# Water_Level_Indicator_shematic.net
KiCad netlist of a schematic drawn in Altium Designer
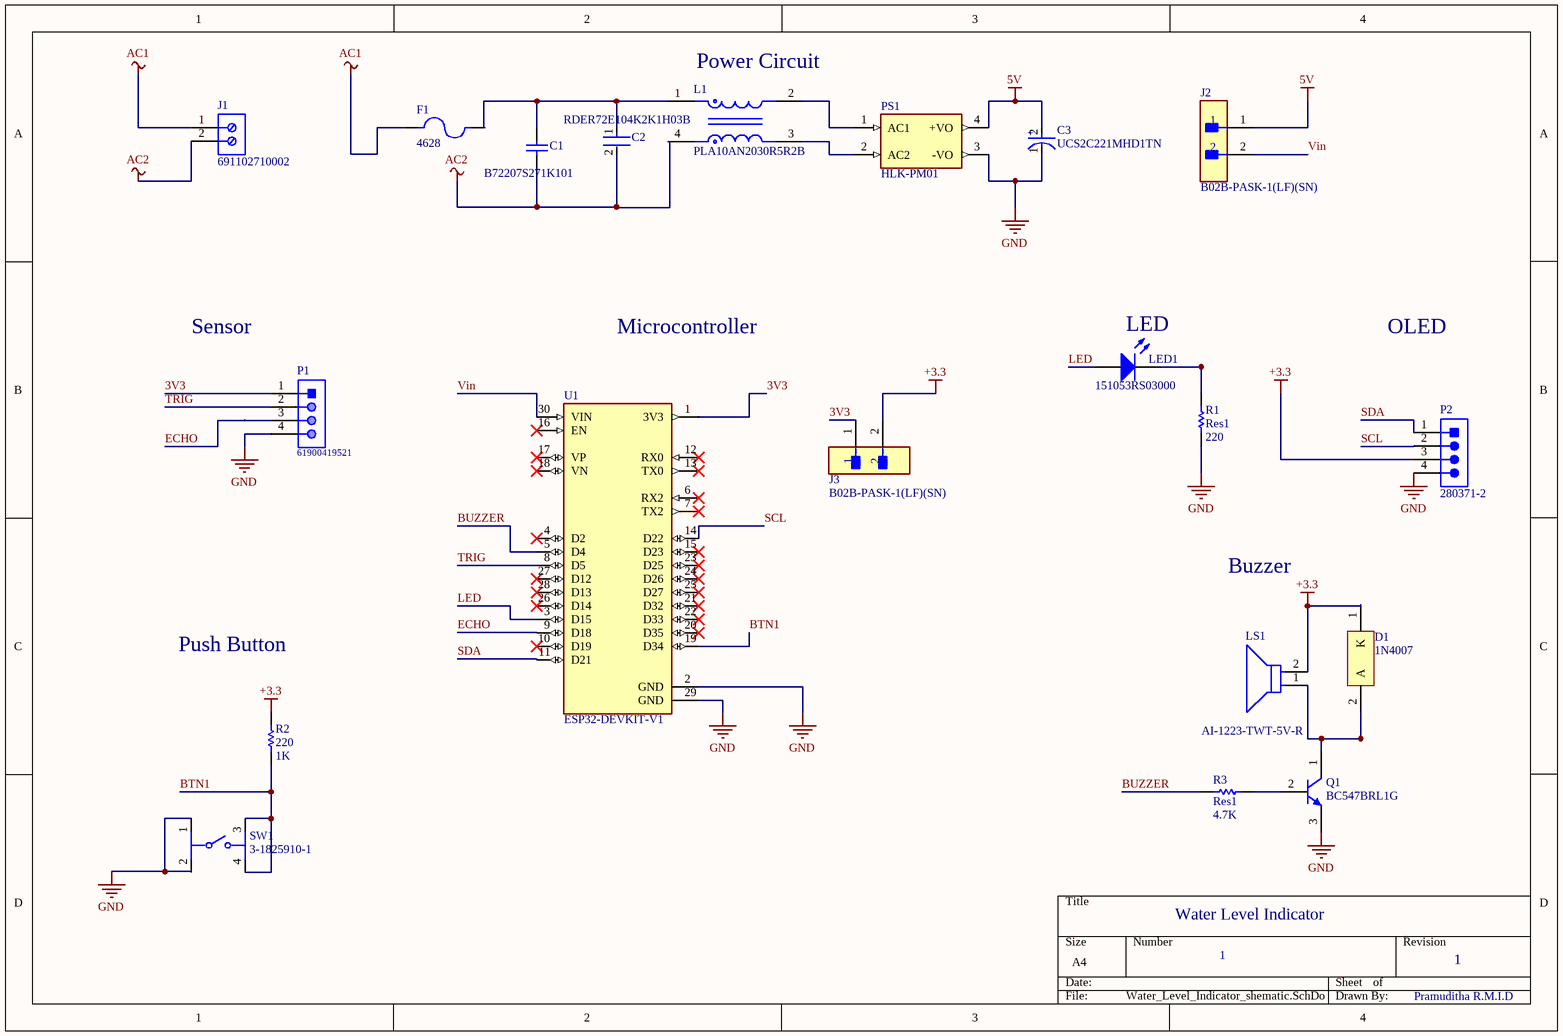
[diagram p0: Water_Level_Indicator_shematic.SchDoc]

(export (version "E")
  (design (tool "Eeschema 10.0.6"))
  (components
    (comp (ref "C1")
      (value "B72207S271K101")
      (footprint "TDK-S07K275")
      (description "Leaded Varistor, 110 pF, 275 Vrms, 1.2 KA, -40 to 85 degC, 2-Pin THD, RoHS, Bulk")
      (fields (field (name "MANUFACTURER") "TDK"))
      (libsource (lib "Altium Content Vault") (part "CAP-NP-2"))
    )
    (comp (ref "C2")
      (value "RDER72E104K2K1H03B")
      (footprint "FP-RDE2M1-MFG")
      (description "Ceramic Capacitor 100nF ±10% 250V X7R Radial")
      (fields (field (name "TOLERANCE") "10%"))
      (libsource (lib "Altium Content Vault") (part "b4654b650e69147ec39a6b967a45e02"))
    )
    (comp (ref "C3")
      (value "UCS2C221MHD1TN")
      (footprint "FP-UCS2C221MHD1TN-MFG")
      (description "CAP ALUM 220UF 20% 160V RADIAL")
      (fields (field (name "TOLERANCE") "20%"))
      (libsource (lib "Altium Content Vault") (part "a00bbbee19879c290e62620ae7e47b1"))
    )
    (comp (ref "D1")
      (value "1N4007")
      (footprint "ONSC-AXIAL_LEAD-2-59-10_P")
      (description "Standard Recovery Rectifier, 2-Pin Axial_Lead, Pb-Free, Bulk Bag")
      (fields (field (name "MANUFACTURER") "On Semiconductor"))
      (libsource (lib "Altium Content Vault") (part "ONSC-D-K1A2-2_A"))
    )
    (comp (ref "F1")
      (value "4628")
      (footprint "FUSE_4628")
      (description "5mm Slim Line Fuse holder")
      (fields (field (name "MF") "Keystone"))
      (libsource (lib "4628") (part "4628"))
    )
    (comp (ref "J1")
      (value "691102710002")
      (footprint "691102710002")
      (description "Series 102 - 5.00 mm Horizontal Entry Modular with Pressure Clamp WR-TBL, 2 pin")
      (fields (field (name "MANUFACTURER") "Wurth Elektronik") (field (name "PUBLISHER") "WurthElektronik"))
      (libsource (lib "Altium Content Vault") (part "WE-CN-1P-F-TB2"))
    )
    (comp (ref "J2")
      (value "B02B-PASK-1(LF)(SN)")
      (footprint "FP-B02B-PASK-1_LF_SN-MFG")
      (description "CONN HEADER VERT 2POS 2MM")
      (libsource (lib "") (part "3bc925449376181038e59eaffc5286c_1"))
    )
    (comp (ref "J3")
      (value "B02B-PASK-1(LF)(SN)")
      (footprint "FP-B02B-PASK-1_LF_SN-MFG")
      (description "CONN HEADER VERT 2POS 2MM")
      (libsource (lib "Altium Content Vault") (part "3bc925449376181038e59eaffc5286c"))
    )
    (comp (ref "L1")
      (value "PLA10AN2030R5R2B")
      (footprint "FP-PLA10A-PLH10A-MFG")
      (description "Common Mode Choke Dual 20mH 0.5A 1.8Ω DCR Thru-Hole Bulk")
      (libsource (lib "Altium Content Vault") (part "48057101139d7a9ca9ebeb60f9e3dee"))
    )
    (comp (ref "LED1")
      (value "151053RS03000")
      (footprint "Type 5mm")
      (description "THT LED round mono-color waterclear,  WL-TMRW ,Red")
      (fields (field (name "MANUFACTURER") "Wuerth Elektronik"))
      (libsource (lib "Altium Content Vault") (part "WE-LED_K1A2-2"))
    )
    (comp (ref "LS1")
      (value "AI-1223-TWT-5V-R")
      (footprint "FP-AI-1223-TWT-5V-R-MFG")
      (description "AUDIO MAGNETIC INDICATOR 3-7V TH")
      (libsource (lib "Altium Content Vault") (part "1973c4b650225fd2ddacaff6b763965"))
    )
    (comp (ref "P1")
      (value "61900419521")
      (footprint "61900419521")
      (description "Male Top Locking Header WR-WTB, THT, Right Angled, pitch 2.54 mm, 1 x 4 position")
      (fields (field (name "MANUFACTURER") "Wurth Elektronik") (field (name "PUBLISHER") "WurthElektronik"))
      (libsource (lib "Altium Content Vault") (part "WE-CN-1P-M-R4"))
    )
    (comp (ref "P2")
      (value "280371-2")
      (footprint "TECO-280371-2_V")
      (fields (field (name "MANUFACTURER") "TE Connectivity"))
      (libsource (lib "Altium Content Vault") (part "CN-1P-M-R4"))
    )
    (comp (ref "PS1")
      (value "HLK-PM01")
      (footprint "CONV_HLK-PM01")
      (fields (field (name "MF") "Hi-link") (field (name "MP") "hlk-pm01"))
      (libsource (lib "HLK-PM01") (part "HLK-PM01"))
    )
    (comp (ref "Q1")
      (value "BC547BRL1G")
      (footprint "ONSC-TO-92-3-29-11_AM_BL")
      (description "Amplifier Transistor, NPN Silicon, 3-Pin TO-92, Pb-Free, Tape and Reel")
      (fields (field (name "MANUFACTURER") "On Semiconductor"))
      (libsource (lib "Altium Content Vault") (part "ONSC-NPN-C1B2E3-3"))
    )
    (comp (ref "R1")
      (value "Res1")
      (footprint "AXIAL-0.3")
      (description "Resistor")
      (fields (field (name "ALTIUM_VALUE") "220") (field (name "PUBLISHER") "Altium Limited"))
      (libsource (lib "Miscellaneous Devices") (part "Res1"))
    )
    (comp (ref "R2")
      (value "220")
      (footprint "AXIAL-0.3")
      (description "Resistor")
      (fields (field (name "ALTIUM_VALUE") "1K") (field (name "PUBLISHER") "Altium Limited"))
      (libsource (lib "Miscellaneous Devices") (part "Res1"))
    )
    (comp (ref "R3")
      (value "Res1")
      (footprint "AXIAL-0.3")
      (description "Resistor")
      (fields (field (name "ALTIUM_VALUE") "4.7K") (field (name "PUBLISHER") "Altium Limited"))
      (libsource (lib "Miscellaneous Devices") (part "Res1"))
    )
    (comp (ref "SW1")
      (value "3-1825910-1")
      (footprint "FP-3-1825910-1-MFG")
      (description "SWITCH TACTILE SPST-NO 0.05A 24V")
      (fields
        (field (name "MANUFACTURER") "TE Connectivity")
        (field (name "OCTOPART") "https://octopart.com/3-1825910-1-te+connectivity-46506874")
      )
      (libsource (lib "Altium Content Vault") (part "b8895f3f4cefb76e1819d2863dba89b"))
    )
    (comp (ref "U1")
      (value "ESP32-DEVKIT-V1")
      (footprint "MODULE_ESP32_DEVKIT_V1")
      (fields (field (name "MF") "Do it"))
      (libsource (lib "ESP32-DEVKIT-V1_mod") (part "ESP32-DEVKIT-V1"))
    )
  )
  (nets
    (net (code "1") (name "+3.3") (class "Default")
      (node (ref "D1") (pin "1") (pinfunction "K_1") (pintype "passive"))
      (node (ref "J3") (pin "2") (pinfunction "2_2") (pintype "passive"))
      (node (ref "LS1") (pin "2") (pinfunction "A_2") (pintype "passive"))
      (node (ref "P2") (pin "3") (pinfunction "3_3") (pintype "passive"))
      (node (ref "R2") (pin "2") (pinfunction "2_2") (pintype "passive"))
    )
    (net (code "2") (name "/3V3") (class "Default")
      (node (ref "J3") (pin "1") (pinfunction "1_1") (pintype "passive"))
      (node (ref "P1") (pin "1") (pinfunction "1_1") (pintype "passive"))
      (node (ref "U1") (pin "1") (pinfunction "3V3_1") (pintype "output"))
    )
    (net (code "3") (name "/BTN1") (class "Default")
      (node (ref "R2") (pin "1") (pinfunction "1_1") (pintype "passive"))
      (node (ref "SW1") (pin "3") (pinfunction "3_3") (pintype "passive"))
      (node (ref "SW1") (pin "4") (pinfunction "4_4") (pintype "passive"))
      (node (ref "U1") (pin "19") (pinfunction "D34_19") (pintype "bidirectional"))
    )
    (net (code "4") (name "/BUZZER") (class "Default")
      (node (ref "R3") (pin "1") (pinfunction "1_1") (pintype "passive"))
      (node (ref "U1") (pin "5") (pinfunction "D4_5") (pintype "bidirectional"))
    )
    (net (code "5") (name "/ECHO") (class "Default")
      (node (ref "P1") (pin "3") (pinfunction "3_3") (pintype "passive"))
      (node (ref "U1") (pin "9") (pinfunction "D18_9") (pintype "bidirectional"))
    )
    (net (code "6") (name "/LED") (class "Default")
      (node (ref "LED1") (pin "2") (pinfunction "A_2") (pintype "passive"))
      (node (ref "U1") (pin "3") (pinfunction "D15_3") (pintype "bidirectional"))
    )
    (net (code "7") (name "/SCL") (class "Default")
      (node (ref "P2") (pin "2") (pinfunction "2_2") (pintype "passive"))
      (node (ref "U1") (pin "14") (pinfunction "D22_14") (pintype "bidirectional"))
    )
    (net (code "8") (name "/SDA") (class "Default")
      (node (ref "P2") (pin "1") (pinfunction "1_1") (pintype "passive"))
      (node (ref "U1") (pin "11") (pinfunction "D21_11") (pintype "bidirectional"))
    )
    (net (code "9") (name "/TRIG") (class "Default")
      (node (ref "P1") (pin "2") (pinfunction "2_2") (pintype "passive"))
      (node (ref "U1") (pin "8") (pinfunction "D5_8") (pintype "bidirectional"))
    )
    (net (code "10") (name "/Vin") (class "Default")
      (node (ref "J2") (pin "2") (pinfunction "2_2") (pintype "passive"))
      (node (ref "U1") (pin "30") (pinfunction "VIN_30") (pintype "input"))
    )
    (net (code "11") (name "5V") (class "Default")
      (node (ref "C3") (pin "2") (pinfunction "A_2") (pintype "passive"))
      (node (ref "J2") (pin "1") (pinfunction "1_1") (pintype "passive"))
      (node (ref "PS1") (pin "4") (pinfunction "+VO_4") (pintype "output"))
    )
    (net (code "12") (name "AC1") (class "Default")
      (node (ref "F1") (pin "1") (pinfunction "1_1") (pintype "passive"))
      (node (ref "J1") (pin "1") (pinfunction "1_1") (pintype "passive"))
    )
    (net (code "13") (name "AC2") (class "Default")
      (node (ref "C1") (pin "1") (pinfunction "1_1") (pintype "passive"))
      (node (ref "C2") (pin "2") (pinfunction "2_2") (pintype "passive"))
      (node (ref "J1") (pin "2") (pinfunction "2_2") (pintype "passive"))
      (node (ref "L1") (pin "4") (pinfunction "4_4") (pintype "passive"))
    )
    (net (code "14") (name "GND") (class "Default")
      (node (ref "C3") (pin "1") (pinfunction "C_1") (pintype "passive"))
      (node (ref "P1") (pin "4") (pinfunction "4_4") (pintype "passive"))
      (node (ref "P2") (pin "4") (pinfunction "4_4") (pintype "passive"))
      (node (ref "PS1") (pin "3") (pinfunction "-VO_3") (pintype "output"))
      (node (ref "Q1") (pin "3") (pinfunction "E_3") (pintype "passive"))
      (node (ref "R1") (pin "2") (pinfunction "2_2") (pintype "passive"))
      (node (ref "SW1") (pin "1") (pinfunction "1_1") (pintype "passive"))
      (node (ref "SW1") (pin "2") (pinfunction "2_2") (pintype "passive"))
      (node (ref "U1") (pin "2") (pinfunction "GND_2") (pintype "power_in"))
      (node (ref "U1") (pin "29") (pinfunction "GND_29") (pintype "power_in"))
    )
    (net (code "15") (name "Net-(C1-Pad2)") (class "Default")
      (node (ref "C1") (pin "2") (pinfunction "2_2") (pintype "passive"))
      (node (ref "C2") (pin "1") (pinfunction "1_1") (pintype "passive"))
      (node (ref "F1") (pin "2") (pinfunction "2_2") (pintype "passive"))
      (node (ref "L1") (pin "1") (pinfunction "1_1") (pintype "passive"))
    )
    (net (code "16") (name "Net-(D1-A)") (class "Default")
      (node (ref "D1") (pin "2") (pinfunction "A_2") (pintype "passive"))
      (node (ref "LS1") (pin "1") (pinfunction "C_1") (pintype "passive"))
      (node (ref "Q1") (pin "1") (pinfunction "C_1") (pintype "passive"))
    )
    (net (code "17") (name "Net-(LED1-K)") (class "Default")
      (node (ref "LED1") (pin "1") (pinfunction "K_1") (pintype "passive"))
      (node (ref "R1") (pin "1") (pinfunction "1_1") (pintype "passive"))
    )
    (net (code "18") (name "Net-(PS1-AC1)") (class "Default")
      (node (ref "L1") (pin "2") (pinfunction "2_2") (pintype "passive"))
      (node (ref "PS1") (pin "1") (pinfunction "AC1_1") (pintype "input"))
    )
    (net (code "19") (name "Net-(PS1-AC2)") (class "Default")
      (node (ref "L1") (pin "3") (pinfunction "3_3") (pintype "passive"))
      (node (ref "PS1") (pin "2") (pinfunction "AC2_2") (pintype "input"))
    )
    (net (code "20") (name "Net-(Q1-B)") (class "Default")
      (node (ref "Q1") (pin "2") (pinfunction "B_2") (pintype "passive"))
      (node (ref "R3") (pin "2") (pinfunction "2_2") (pintype "passive"))
    )
    (net (code "21") (name "unconnected-(U1-D2-Pad4)") (class "Default")
      (node (ref "U1") (pin "4") (pinfunction "D2_4") (pintype "bidirectional+no_connect"))
    )
    (net (code "22") (name "unconnected-(U1-D12-Pad27)") (class "Default")
      (node (ref "U1") (pin "27") (pinfunction "D12_27") (pintype "bidirectional+no_connect"))
    )
    (net (code "23") (name "unconnected-(U1-D13-Pad28)") (class "Default")
      (node (ref "U1") (pin "28") (pinfunction "D13_28") (pintype "bidirectional+no_connect"))
    )
    (net (code "24") (name "unconnected-(U1-D14-Pad26)") (class "Default")
      (node (ref "U1") (pin "26") (pinfunction "D14_26") (pintype "bidirectional+no_connect"))
    )
    (net (code "25") (name "unconnected-(U1-D19-Pad10)") (class "Default")
      (node (ref "U1") (pin "10") (pinfunction "D19_10") (pintype "bidirectional+no_connect"))
    )
    (net (code "26") (name "unconnected-(U1-D23-Pad15)") (class "Default")
      (node (ref "U1") (pin "15") (pinfunction "D23_15") (pintype "bidirectional+no_connect"))
    )
    (net (code "27") (name "unconnected-(U1-D25-Pad23)") (class "Default")
      (node (ref "U1") (pin "23") (pinfunction "D25_23") (pintype "bidirectional+no_connect"))
    )
    (net (code "28") (name "unconnected-(U1-D26-Pad24)") (class "Default")
      (node (ref "U1") (pin "24") (pinfunction "D26_24") (pintype "bidirectional+no_connect"))
    )
    (net (code "29") (name "unconnected-(U1-D27-Pad25)") (class "Default")
      (node (ref "U1") (pin "25") (pinfunction "D27_25") (pintype "bidirectional+no_connect"))
    )
    (net (code "30") (name "unconnected-(U1-D32-Pad21)") (class "Default")
      (node (ref "U1") (pin "21") (pinfunction "D32_21") (pintype "bidirectional+no_connect"))
    )
    (net (code "31") (name "unconnected-(U1-D33-Pad22)") (class "Default")
      (node (ref "U1") (pin "22") (pinfunction "D33_22") (pintype "bidirectional+no_connect"))
    )
    (net (code "32") (name "unconnected-(U1-D35-Pad20)") (class "Default")
      (node (ref "U1") (pin "20") (pinfunction "D35_20") (pintype "bidirectional+no_connect"))
    )
    (net (code "33") (name "unconnected-(U1-EN-Pad16)") (class "Default")
      (node (ref "U1") (pin "16") (pinfunction "EN_16") (pintype "input+no_connect"))
    )
    (net (code "34") (name "unconnected-(U1-RX0-Pad12)") (class "Default")
      (node (ref "U1") (pin "12") (pinfunction "RX0_12") (pintype "input+no_connect"))
    )
    (net (code "35") (name "unconnected-(U1-RX2-Pad6)") (class "Default")
      (node (ref "U1") (pin "6") (pinfunction "RX2_6") (pintype "input+no_connect"))
    )
    (net (code "36") (name "unconnected-(U1-TX0-Pad13)") (class "Default")
      (node (ref "U1") (pin "13") (pinfunction "TX0_13") (pintype "output+no_connect"))
    )
    (net (code "37") (name "unconnected-(U1-TX2-Pad7)") (class "Default")
      (node (ref "U1") (pin "7") (pinfunction "TX2_7") (pintype "output+no_connect"))
    )
    (net (code "38") (name "unconnected-(U1-VN-Pad18)") (class "Default")
      (node (ref "U1") (pin "18") (pinfunction "VN_18") (pintype "bidirectional+no_connect"))
    )
    (net (code "39") (name "unconnected-(U1-VP-Pad17)") (class "Default")
      (node (ref "U1") (pin "17") (pinfunction "VP_17") (pintype "bidirectional+no_connect"))
    )
  )
)
